# Reles.net
KiCad netlist of a schematic drawn in Altium Designer
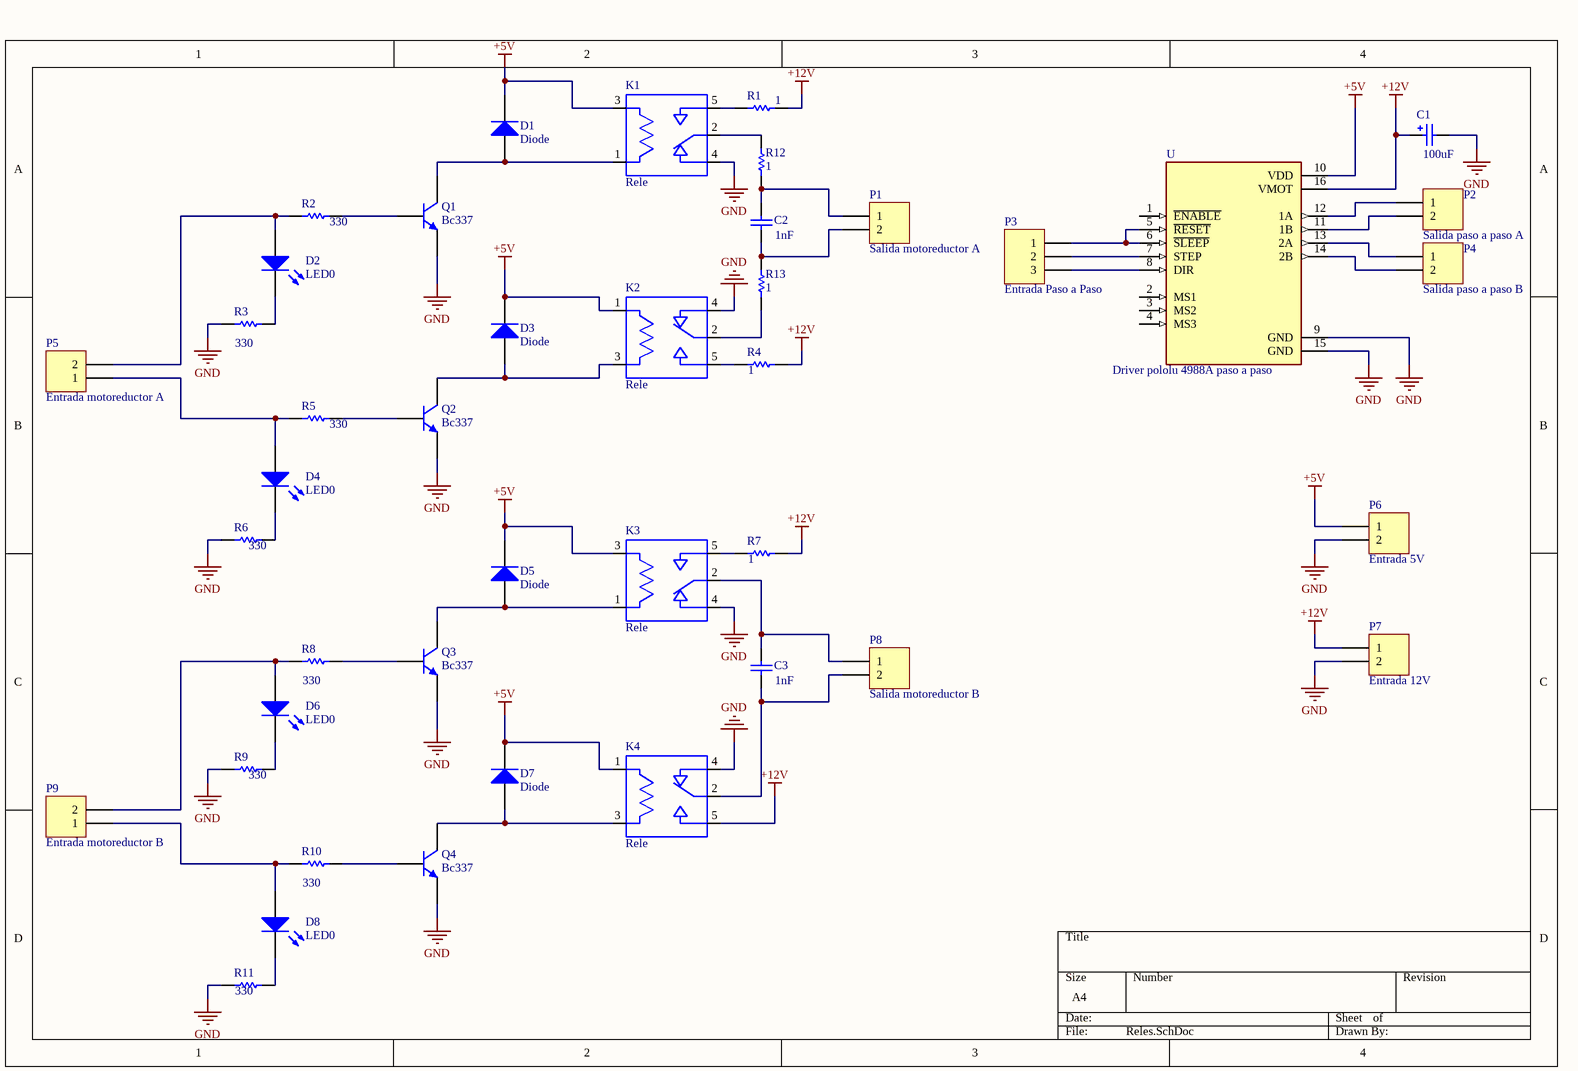
[diagram p0: Reles.SchDoc]

(export (version "E")
  (design (tool "Eeschema 10.0.6"))
  (components
    (comp (ref "C1")
      (value "100uF")
      (footprint "RAD-0.1")
      (description "Polarized Capacitor (Axial)")
      (fields (field (name "Comment") "Cap Pol2") (field (name "PUBLISHER") "Altium Limited"))
      (libsource (lib "Miscellaneous Devices") (part "Cap Pol2"))
    )
    (comp (ref "C2")
      (value "1nF")
      (footprint "RAD-0.1")
      (description "Capacitor")
      (fields (field (name "Comment") "Cap") (field (name "PUBLISHER") "Altium Limited"))
      (libsource (lib "Miscellaneous Devices") (part "Cap"))
    )
    (comp (ref "C3")
      (value "1nF")
      (footprint "RAD-0.1")
      (description "Capacitor")
      (fields (field (name "Comment") "Cap") (field (name "PUBLISHER") "Altium Limited"))
      (libsource (lib "Miscellaneous Devices") (part "Cap"))
    )
    (comp (ref "D1")
      (value "Diode")
      (footprint "DIODE-0.4")
      (description "Default Diode")
      (fields (field (name "PUBLISHER") "Altium Limited"))
      (libsource (lib "Miscellaneous Devices") (part "Diode"))
    )
    (comp (ref "D2")
      (value "LED0")
      (footprint "BAT-2")
      (description "Typical INFRARED GaAs LED")
      (fields (field (name "PUBLISHER") "Altium Limited"))
      (libsource (lib "Miscellaneous Devices") (part "LED0"))
    )
    (comp (ref "D3")
      (value "Diode")
      (footprint "DIODE-0.4")
      (description "Default Diode")
      (fields (field (name "PUBLISHER") "Altium Limited"))
      (libsource (lib "Miscellaneous Devices") (part "Diode"))
    )
    (comp (ref "D4")
      (value "LED0")
      (footprint "BAT-2")
      (description "Typical INFRARED GaAs LED")
      (fields (field (name "PUBLISHER") "Altium Limited"))
      (libsource (lib "Miscellaneous Devices") (part "LED0"))
    )
    (comp (ref "D5")
      (value "Diode")
      (footprint "DIODE-0.4")
      (description "Default Diode")
      (fields (field (name "PUBLISHER") "Altium Limited"))
      (libsource (lib "Miscellaneous Devices") (part "Diode"))
    )
    (comp (ref "D6")
      (value "LED0")
      (footprint "BAT-2")
      (description "Typical INFRARED GaAs LED")
      (fields (field (name "PUBLISHER") "Altium Limited"))
      (libsource (lib "Miscellaneous Devices") (part "LED0"))
    )
    (comp (ref "D7")
      (value "Diode")
      (footprint "DIODE-0.4")
      (description "Default Diode")
      (fields (field (name "PUBLISHER") "Altium Limited"))
      (libsource (lib "Miscellaneous Devices") (part "Diode"))
    )
    (comp (ref "D8")
      (value "LED0")
      (footprint "BAT-2")
      (description "Typical INFRARED GaAs LED")
      (fields (field (name "PUBLISHER") "Altium Limited"))
      (libsource (lib "Miscellaneous Devices") (part "LED0"))
    )
    (comp (ref "K1")
      (value "1-1721150-0")
      (footprint "RELAY_1-1721150-0")
      (description "General Purpose Relay SPDT (1 Form C) 5VDC Coil Through Hole")
      (fields (field (name "MF") "TE Connectivity") (field (name "COMMENT_1") "Rele"))
      (libsource (lib "1-1721150-0") (part "1-1721150-0"))
    )
    (comp (ref "K2")
      (value "1-1721150-0")
      (footprint "RELAY_1-1721150-0")
      (description "General Purpose Relay SPDT (1 Form C) 5VDC Coil Through Hole")
      (fields (field (name "MF") "TE Connectivity") (field (name "COMMENT_1") "Rele"))
      (libsource (lib "1-1721150-0") (part "1-1721150-0"))
    )
    (comp (ref "K3")
      (value "1-1721150-0")
      (footprint "RELAY_1-1721150-0")
      (description "General Purpose Relay SPDT (1 Form C) 5VDC Coil Through Hole")
      (fields (field (name "MF") "TE Connectivity") (field (name "COMMENT_1") "Rele"))
      (libsource (lib "1-1721150-0") (part "1-1721150-0"))
    )
    (comp (ref "K4")
      (value "1-1721150-0")
      (footprint "RELAY_1-1721150-0")
      (description "General Purpose Relay SPDT (1 Form C) 5VDC Coil Through Hole")
      (fields (field (name "MF") "TE Connectivity") (field (name "COMMENT_1") "Rele"))
      (libsource (lib "1-1721150-0") (part "1-1721150-0"))
    )
    (comp (ref "P1")
      (value "Salida motoreductor A")
      (footprint "TE_282841-2")
      (description "Header, 2-Pin")
      (fields (field (name "PUBLISHER") "Altium Limited"))
      (libsource (lib "Miscellaneous Connectors") (part "MHDR1X2"))
    )
    (comp (ref "P2")
      (value "Salida paso a paso A")
      (footprint "TE_282841-2")
      (description "Header, 2-Pin")
      (fields (field (name "PUBLISHER") "Altium Limited"))
      (libsource (lib "Miscellaneous Connectors") (part "MHDR1X2"))
    )
    (comp (ref "P3")
      (value "Entrada Paso a Paso")
      (footprint "TE_1776275-3")
      (description "Header, 3-Pin")
      (fields (field (name "PUBLISHER") "Altium Limited"))
      (libsource (lib "Miscellaneous Connectors") (part "MHDR1X3"))
    )
    (comp (ref "P4")
      (value "Salida paso a paso B")
      (footprint "TE_282841-2")
      (description "Header, 2-Pin")
      (fields (field (name "PUBLISHER") "Altium Limited"))
      (libsource (lib "Miscellaneous Connectors") (part "MHDR1X2"))
    )
    (comp (ref "P5")
      (value "Entrada motoreductor A")
      (footprint "TE_282841-2")
      (description "Header, 2-Pin")
      (fields (field (name "PUBLISHER") "Altium Limited"))
      (libsource (lib "") (part "MHDR1X2_1"))
    )
    (comp (ref "P6")
      (value "Entrada 5V")
      (footprint "TE_282841-2")
      (description "Header, 2-Pin")
      (fields (field (name "PUBLISHER") "Altium Limited"))
      (libsource (lib "Miscellaneous Connectors") (part "MHDR1X2"))
    )
    (comp (ref "P7")
      (value "Entrada 12V")
      (footprint "TE_282841-2")
      (description "Header, 2-Pin")
      (fields (field (name "PUBLISHER") "Altium Limited"))
      (libsource (lib "Miscellaneous Connectors") (part "MHDR1X2"))
    )
    (comp (ref "P8")
      (value "Salida motoreductor B")
      (footprint "TE_282841-2")
      (description "Header, 2-Pin")
      (fields (field (name "PUBLISHER") "Altium Limited"))
      (libsource (lib "Miscellaneous Connectors") (part "MHDR1X2"))
    )
    (comp (ref "P9")
      (value "Entrada motoreductor B")
      (footprint "TE_282841-2")
      (description "Header, 2-Pin")
      (fields (field (name "PUBLISHER") "Altium Limited"))
      (libsource (lib "") (part "MHDR1X2_1"))
    )
    (comp (ref "Q1")
      (value "Bc337")
      (footprint "TO92254P520H877-3")
      (description "NPN General Purpose Amplifier")
      (fields (field (name "PUBLISHER") "Altium Limited"))
      (libsource (lib "Miscellaneous Devices") (part "2N3904"))
    )
    (comp (ref "Q2")
      (value "Bc337")
      (footprint "TO92254P520H877-3")
      (description "NPN General Purpose Amplifier")
      (fields (field (name "PUBLISHER") "Altium Limited"))
      (libsource (lib "Miscellaneous Devices") (part "2N3904"))
    )
    (comp (ref "Q3")
      (value "Bc337")
      (footprint "TO92254P520H877-3")
      (description "NPN General Purpose Amplifier")
      (fields (field (name "PUBLISHER") "Altium Limited"))
      (libsource (lib "Miscellaneous Devices") (part "2N3904"))
    )
    (comp (ref "Q4")
      (value "Bc337")
      (footprint "TO92254P520H877-3")
      (description "NPN General Purpose Amplifier")
      (fields (field (name "PUBLISHER") "Altium Limited"))
      (libsource (lib "Miscellaneous Devices") (part "2N3904"))
    )
    (comp (ref "R1")
      (value "1")
      (footprint "AXIAL-0.3")
      (description "Resistor")
      (fields (field (name "Comment") "Res1") (field (name "PUBLISHER") "Altium Limited"))
      (libsource (lib "Miscellaneous Devices") (part "Res1"))
    )
    (comp (ref "R2")
      (value "330")
      (footprint "AXIAL-0.3")
      (description "Resistor")
      (fields (field (name "Comment") "Res1") (field (name "PUBLISHER") "Altium Limited"))
      (libsource (lib "Miscellaneous Devices") (part "Res1"))
    )
    (comp (ref "R3")
      (value "330")
      (footprint "AXIAL-0.3")
      (description "Resistor")
      (fields (field (name "Comment") "Res1") (field (name "PUBLISHER") "Altium Limited"))
      (libsource (lib "Miscellaneous Devices") (part "Res1"))
    )
    (comp (ref "R4")
      (value "1")
      (footprint "AXIAL-0.3")
      (description "Resistor")
      (fields (field (name "Comment") "Res1") (field (name "PUBLISHER") "Altium Limited"))
      (libsource (lib "Miscellaneous Devices") (part "Res1"))
    )
    (comp (ref "R5")
      (value "330")
      (footprint "AXIAL-0.3")
      (description "Resistor")
      (fields (field (name "Comment") "Res1") (field (name "PUBLISHER") "Altium Limited"))
      (libsource (lib "Miscellaneous Devices") (part "Res1"))
    )
    (comp (ref "R6")
      (value "330")
      (footprint "AXIAL-0.3")
      (description "Resistor")
      (fields (field (name "Comment") "Res1") (field (name "PUBLISHER") "Altium Limited"))
      (libsource (lib "Miscellaneous Devices") (part "Res1"))
    )
    (comp (ref "R7")
      (value "1")
      (footprint "AXIAL-0.3")
      (description "Resistor")
      (fields (field (name "Comment") "Res1") (field (name "PUBLISHER") "Altium Limited"))
      (libsource (lib "Miscellaneous Devices") (part "Res1"))
    )
    (comp (ref "R8")
      (value "330")
      (footprint "AXIAL-0.3")
      (description "Resistor")
      (fields (field (name "Comment") "Res1") (field (name "PUBLISHER") "Altium Limited"))
      (libsource (lib "Miscellaneous Devices") (part "Res1"))
    )
    (comp (ref "R9")
      (value "330")
      (footprint "AXIAL-0.3")
      (description "Resistor")
      (fields (field (name "Comment") "Res1") (field (name "PUBLISHER") "Altium Limited"))
      (libsource (lib "Miscellaneous Devices") (part "Res1"))
    )
    (comp (ref "R10")
      (value "330")
      (footprint "AXIAL-0.3")
      (description "Resistor")
      (fields (field (name "Comment") "Res1") (field (name "PUBLISHER") "Altium Limited"))
      (libsource (lib "Miscellaneous Devices") (part "Res1"))
    )
    (comp (ref "R11")
      (value "330")
      (footprint "AXIAL-0.3")
      (description "Resistor")
      (fields (field (name "Comment") "Res1") (field (name "PUBLISHER") "Altium Limited"))
      (libsource (lib "Miscellaneous Devices") (part "Res1"))
    )
    (comp (ref "R12")
      (value "1")
      (footprint "AXIAL-0.3")
      (description "Resistor")
      (fields (field (name "Comment") "Res1") (field (name "PUBLISHER") "Altium Limited"))
      (libsource (lib "Miscellaneous Devices") (part "Res1"))
    )
    (comp (ref "R13")
      (value "1")
      (footprint "AXIAL-0.3")
      (description "Resistor")
      (fields (field (name "Comment") "Res1") (field (name "PUBLISHER") "Altium Limited"))
      (libsource (lib "Miscellaneous Devices") (part "Res1"))
    )
    (comp (ref "U")
      (value "Driver pololu 4988A paso a paso")
      (footprint "MODULE_A4988_STEPPER_MOTOR_DRIVER_CARRIER")
      (description "Stepper Motor Driver")
      (fields (field (name "MP") "A4988 STEPPER MOTOR DRIVER CARRIER") (field (name "MF") "Pololu"))
      (libsource (lib "A4988_STEPPER_MOTOR_DRIVER_CARRIER") (part "A4988_STEPPER_MOTOR_DRIVER_CARRIER"))
    )
  )
  (nets
    (net (code "1") (name "+5V") (class "Default")
      (node (ref "D1") (pin "2") (pinfunction "K_2") (pintype "passive"))
      (node (ref "D3") (pin "2") (pinfunction "K_2") (pintype "passive"))
      (node (ref "D5") (pin "2") (pinfunction "K_2") (pintype "passive"))
      (node (ref "D7") (pin "2") (pinfunction "K_2") (pintype "passive"))
      (node (ref "K1") (pin "3") (pinfunction "3_3") (pintype "passive"))
      (node (ref "K2") (pin "1") (pinfunction "1_1") (pintype "passive"))
      (node (ref "K3") (pin "3") (pinfunction "3_3") (pintype "passive"))
      (node (ref "K4") (pin "1") (pinfunction "1_1") (pintype "passive"))
      (node (ref "P6") (pin "1") (pinfunction "1_1") (pintype "passive"))
      (node (ref "U") (pin "10") (pinfunction "VDD_10") (pintype "power_in"))
    )
    (net (code "2") (name "+12V") (class "Default")
      (node (ref "C1") (pin "1") (pinfunction "1_1") (pintype "passive"))
      (node (ref "K4") (pin "5") (pinfunction "5_5") (pintype "passive"))
      (node (ref "P7") (pin "1") (pinfunction "1_1") (pintype "passive"))
      (node (ref "R1") (pin "2") (pinfunction "2_2") (pintype "passive"))
      (node (ref "R4") (pin "2") (pinfunction "2_2") (pintype "passive"))
      (node (ref "R7") (pin "2") (pinfunction "2_2") (pintype "passive"))
      (node (ref "U") (pin "16") (pinfunction "VMOT_16") (pintype "power_in"))
    )
    (net (code "3") (name "GND") (class "Default")
      (node (ref "C1") (pin "2") (pinfunction "2_2") (pintype "passive"))
      (node (ref "K1") (pin "4") (pinfunction "4_4") (pintype "passive"))
      (node (ref "K2") (pin "4") (pinfunction "4_4") (pintype "passive"))
      (node (ref "K3") (pin "4") (pinfunction "4_4") (pintype "passive"))
      (node (ref "K4") (pin "4") (pinfunction "4_4") (pintype "passive"))
      (node (ref "P6") (pin "2") (pinfunction "2_2") (pintype "passive"))
      (node (ref "P7") (pin "2") (pinfunction "2_2") (pintype "passive"))
      (node (ref "Q1") (pin "1") (pinfunction "E_1") (pintype "passive"))
      (node (ref "Q2") (pin "1") (pinfunction "E_1") (pintype "passive"))
      (node (ref "Q3") (pin "1") (pinfunction "E_1") (pintype "passive"))
      (node (ref "Q4") (pin "1") (pinfunction "E_1") (pintype "passive"))
      (node (ref "R11") (pin "1") (pinfunction "1_1") (pintype "passive"))
      (node (ref "R3") (pin "1") (pinfunction "1_1") (pintype "passive"))
      (node (ref "R6") (pin "1") (pinfunction "1_1") (pintype "passive"))
      (node (ref "R9") (pin "1") (pinfunction "1_1") (pintype "passive"))
      (node (ref "U") (pin "15") (pinfunction "GND_15") (pintype "power_in"))
      (node (ref "U") (pin "9") (pinfunction "GND_9") (pintype "power_in"))
    )
    (net (code "4") (name "Net-(C2-Pad1)") (class "Default")
      (node (ref "C2") (pin "1") (pinfunction "1_1") (pintype "passive"))
      (node (ref "P1") (pin "2") (pinfunction "2_2") (pintype "passive"))
      (node (ref "R13") (pin "2") (pinfunction "2_2") (pintype "passive"))
    )
    (net (code "5") (name "Net-(C2-Pad2)") (class "Default")
      (node (ref "C2") (pin "2") (pinfunction "2_2") (pintype "passive"))
      (node (ref "P1") (pin "1") (pinfunction "1_1") (pintype "passive"))
      (node (ref "R12") (pin "2") (pinfunction "2_2") (pintype "passive"))
    )
    (net (code "6") (name "Net-(C3-Pad1)") (class "Default")
      (node (ref "C3") (pin "1") (pinfunction "1_1") (pintype "passive"))
      (node (ref "K4") (pin "2") (pinfunction "2_2") (pintype "passive"))
      (node (ref "P8") (pin "2") (pinfunction "2_2") (pintype "passive"))
    )
    (net (code "7") (name "Net-(C3-Pad2)") (class "Default")
      (node (ref "C3") (pin "2") (pinfunction "2_2") (pintype "passive"))
      (node (ref "K3") (pin "2") (pinfunction "2_2") (pintype "passive"))
      (node (ref "P8") (pin "1") (pinfunction "1_1") (pintype "passive"))
    )
    (net (code "8") (name "Net-(D1-A)") (class "Default")
      (node (ref "D1") (pin "1") (pinfunction "A_1") (pintype "passive"))
      (node (ref "K1") (pin "1") (pinfunction "1_1") (pintype "passive"))
      (node (ref "Q1") (pin "3") (pinfunction "C_3") (pintype "passive"))
    )
    (net (code "9") (name "Net-(D2-A)") (class "Default")
      (node (ref "D2") (pin "1") (pinfunction "A_1") (pintype "passive"))
      (node (ref "P5") (pin "2") (pinfunction "2_2") (pintype "passive"))
      (node (ref "R2") (pin "1") (pinfunction "1_1") (pintype "passive"))
    )
    (net (code "10") (name "Net-(D2-K)") (class "Default")
      (node (ref "D2") (pin "2") (pinfunction "K_2") (pintype "passive"))
      (node (ref "R3") (pin "2") (pinfunction "2_2") (pintype "passive"))
    )
    (net (code "11") (name "Net-(D3-A)") (class "Default")
      (node (ref "D3") (pin "1") (pinfunction "A_1") (pintype "passive"))
      (node (ref "K2") (pin "3") (pinfunction "3_3") (pintype "passive"))
      (node (ref "Q2") (pin "3") (pinfunction "C_3") (pintype "passive"))
    )
    (net (code "12") (name "Net-(D4-A)") (class "Default")
      (node (ref "D4") (pin "1") (pinfunction "A_1") (pintype "passive"))
      (node (ref "P5") (pin "1") (pinfunction "1_1") (pintype "passive"))
      (node (ref "R5") (pin "1") (pinfunction "1_1") (pintype "passive"))
    )
    (net (code "13") (name "Net-(D4-K)") (class "Default")
      (node (ref "D4") (pin "2") (pinfunction "K_2") (pintype "passive"))
      (node (ref "R6") (pin "2") (pinfunction "2_2") (pintype "passive"))
    )
    (net (code "14") (name "Net-(D5-A)") (class "Default")
      (node (ref "D5") (pin "1") (pinfunction "A_1") (pintype "passive"))
      (node (ref "K3") (pin "1") (pinfunction "1_1") (pintype "passive"))
      (node (ref "Q3") (pin "3") (pinfunction "C_3") (pintype "passive"))
    )
    (net (code "15") (name "Net-(D6-A)") (class "Default")
      (node (ref "D6") (pin "1") (pinfunction "A_1") (pintype "passive"))
      (node (ref "P9") (pin "2") (pinfunction "2_2") (pintype "passive"))
      (node (ref "R8") (pin "1") (pinfunction "1_1") (pintype "passive"))
    )
    (net (code "16") (name "Net-(D6-K)") (class "Default")
      (node (ref "D6") (pin "2") (pinfunction "K_2") (pintype "passive"))
      (node (ref "R9") (pin "2") (pinfunction "2_2") (pintype "passive"))
    )
    (net (code "17") (name "Net-(D7-A)") (class "Default")
      (node (ref "D7") (pin "1") (pinfunction "A_1") (pintype "passive"))
      (node (ref "K4") (pin "3") (pinfunction "3_3") (pintype "passive"))
      (node (ref "Q4") (pin "3") (pinfunction "C_3") (pintype "passive"))
    )
    (net (code "18") (name "Net-(D8-A)") (class "Default")
      (node (ref "D8") (pin "1") (pinfunction "A_1") (pintype "passive"))
      (node (ref "P9") (pin "1") (pinfunction "1_1") (pintype "passive"))
      (node (ref "R10") (pin "1") (pinfunction "1_1") (pintype "passive"))
    )
    (net (code "19") (name "Net-(D8-K)") (class "Default")
      (node (ref "D8") (pin "2") (pinfunction "K_2") (pintype "passive"))
      (node (ref "R11") (pin "2") (pinfunction "2_2") (pintype "passive"))
    )
    (net (code "20") (name "Net-(K1-Pad2)") (class "Default")
      (node (ref "K1") (pin "2") (pinfunction "2_2") (pintype "passive"))
      (node (ref "R12") (pin "1") (pinfunction "1_1") (pintype "passive"))
    )
    (net (code "21") (name "Net-(K1-Pad5)") (class "Default")
      (node (ref "K1") (pin "5") (pinfunction "5_5") (pintype "passive"))
      (node (ref "R1") (pin "1") (pinfunction "1_1") (pintype "passive"))
    )
    (net (code "22") (name "Net-(K2-Pad2)") (class "Default")
      (node (ref "K2") (pin "2") (pinfunction "2_2") (pintype "passive"))
      (node (ref "R13") (pin "1") (pinfunction "1_1") (pintype "passive"))
    )
    (net (code "23") (name "Net-(K2-Pad5)") (class "Default")
      (node (ref "K2") (pin "5") (pinfunction "5_5") (pintype "passive"))
      (node (ref "R4") (pin "1") (pinfunction "1_1") (pintype "passive"))
    )
    (net (code "24") (name "Net-(K3-Pad5)") (class "Default")
      (node (ref "K3") (pin "5") (pinfunction "5_5") (pintype "passive"))
      (node (ref "R7") (pin "1") (pinfunction "1_1") (pintype "passive"))
    )
    (net (code "25") (name "Net-(Q1-B)") (class "Default")
      (node (ref "Q1") (pin "2") (pinfunction "B_2") (pintype "passive"))
      (node (ref "R2") (pin "2") (pinfunction "2_2") (pintype "passive"))
    )
    (net (code "26") (name "Net-(Q2-B)") (class "Default")
      (node (ref "Q2") (pin "2") (pinfunction "B_2") (pintype "passive"))
      (node (ref "R5") (pin "2") (pinfunction "2_2") (pintype "passive"))
    )
    (net (code "27") (name "Net-(Q3-B)") (class "Default")
      (node (ref "Q3") (pin "2") (pinfunction "B_2") (pintype "passive"))
      (node (ref "R8") (pin "2") (pinfunction "2_2") (pintype "passive"))
    )
    (net (code "28") (name "Net-(Q4-B)") (class "Default")
      (node (ref "Q4") (pin "2") (pinfunction "B_2") (pintype "passive"))
      (node (ref "R10") (pin "2") (pinfunction "2_2") (pintype "passive"))
    )
    (net (code "29") (name "Net-(U-1A)") (class "Default")
      (node (ref "P2") (pin "1") (pinfunction "1_1") (pintype "passive"))
      (node (ref "U") (pin "12") (pinfunction "1A_12") (pintype "output"))
    )
    (net (code "30") (name "Net-(U-1B)") (class "Default")
      (node (ref "P2") (pin "2") (pinfunction "2_2") (pintype "passive"))
      (node (ref "U") (pin "11") (pinfunction "1B_11") (pintype "output"))
    )
    (net (code "31") (name "Net-(U-2A)") (class "Default")
      (node (ref "P4") (pin "1") (pinfunction "1_1") (pintype "passive"))
      (node (ref "U") (pin "13") (pinfunction "2A_13") (pintype "output"))
    )
    (net (code "32") (name "Net-(U-2B)") (class "Default")
      (node (ref "P4") (pin "2") (pinfunction "2_2") (pintype "passive"))
      (node (ref "U") (pin "14") (pinfunction "2B_14") (pintype "output"))
    )
    (net (code "33") (name "Net-(U-DIR)") (class "Default")
      (node (ref "P3") (pin "3") (pinfunction "3_3") (pintype "passive"))
      (node (ref "U") (pin "8") (pinfunction "DIR_8") (pintype "input"))
    )
    (net (code "34") (name "Net-(U-STEP)") (class "Default")
      (node (ref "P3") (pin "2") (pinfunction "2_2") (pintype "passive"))
      (node (ref "U") (pin "7") (pinfunction "STEP_7") (pintype "input"))
    )
    (net (code "35") (name "Net-(U-~{RESET})") (class "Default")
      (node (ref "P3") (pin "1") (pinfunction "1_1") (pintype "passive"))
      (node (ref "U") (pin "5") (pinfunction "~{RESET}_5") (pintype "input"))
      (node (ref "U") (pin "6") (pinfunction "~{SLEEP}_6") (pintype "input"))
    )
    (net (code "36") (name "unconnected-(U-MS1-Pad2)") (class "Default")
      (node (ref "U") (pin "2") (pinfunction "MS1_2") (pintype "input"))
    )
    (net (code "37") (name "unconnected-(U-MS2-Pad3)") (class "Default")
      (node (ref "U") (pin "3") (pinfunction "MS2_3") (pintype "input"))
    )
    (net (code "38") (name "unconnected-(U-MS3-Pad4)") (class "Default")
      (node (ref "U") (pin "4") (pinfunction "MS3_4") (pintype "input"))
    )
    (net (code "39") (name "unconnected-(U-~{ENABLE}-Pad1)") (class "Default")
      (node (ref "U") (pin "1") (pinfunction "~{ENABLE}_1") (pintype "input"))
    )
  )
)
